# Placa_5_Sensores.net
KiCad netlist of a schematic drawn in Altium Designer
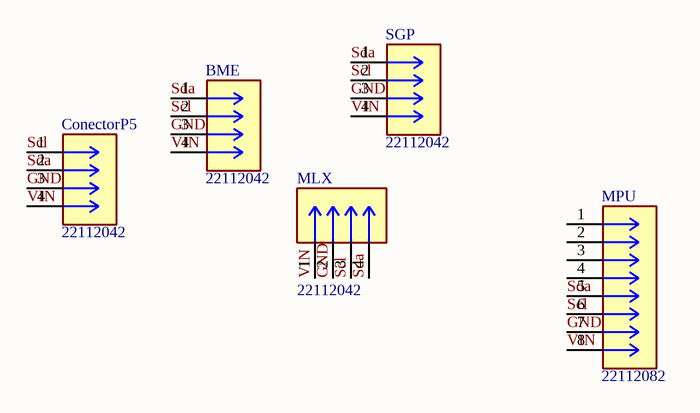
[diagram p0: Placa 5 (Sensores).SchDoc]

(export (version "E")
  (design (tool "Eeschema 10.0.6"))
  (components
    (comp (ref "BME")
      (value "22112042")
      (footprint "CONN_A-6373-04A_MOL")
      (libsource (lib "22112042") (part "22112042"))
    )
    (comp (ref "ConectorP5")
      (value "22112042")
      (footprint "CONN_A-6373-04A_MOL")
      (libsource (lib "22112042") (part "22112042"))
    )
    (comp (ref "MLX")
      (value "22112042")
      (footprint "CONN_A-6373-04A_MOL")
      (libsource (lib "") (part "22112042_1"))
    )
    (comp (ref "MPU")
      (value "22112082")
      (footprint "CONN_A-6373-08A_MOL")
      (description "KKÂ® 254 Solid Header, Vertical, with Friction Lock, 8 Circuits, Gold (Au) Plating")
      (fields (field (name "MF") "Molex") (field (name "MP") "22-11-2082"))
      (libsource (lib "22112082") (part "22112082"))
    )
    (comp (ref "SGP")
      (value "22112042")
      (footprint "CONN_A-6373-04A_MOL")
      (libsource (lib "22112042") (part "22112042"))
    )
  )
  (nets
    (net (code "1") (name "/GND") (class "Default")
      (node (ref "BME") (pin "3") (pinfunction "3_3") (pintype "passive"))
      (node (ref "ConectorP5") (pin "3") (pinfunction "3_3") (pintype "passive"))
      (node (ref "MLX") (pin "2") (pinfunction "2_2") (pintype "passive"))
      (node (ref "MPU") (pin "7") (pinfunction "7_7") (pintype "passive"))
      (node (ref "SGP") (pin "3") (pinfunction "3_3") (pintype "passive"))
    )
    (net (code "2") (name "/Scl") (class "Default")
      (node (ref "BME") (pin "2") (pinfunction "2_2") (pintype "passive"))
      (node (ref "ConectorP5") (pin "1") (pinfunction "1_1") (pintype "passive"))
      (node (ref "MLX") (pin "3") (pinfunction "3_3") (pintype "passive"))
      (node (ref "MPU") (pin "6") (pinfunction "6_6") (pintype "passive"))
      (node (ref "SGP") (pin "2") (pinfunction "2_2") (pintype "passive"))
    )
    (net (code "3") (name "/Sda") (class "Default")
      (node (ref "BME") (pin "1") (pinfunction "1_1") (pintype "passive"))
      (node (ref "ConectorP5") (pin "2") (pinfunction "2_2") (pintype "passive"))
      (node (ref "MLX") (pin "4") (pinfunction "4_4") (pintype "passive"))
      (node (ref "MPU") (pin "5") (pinfunction "5_5") (pintype "passive"))
      (node (ref "SGP") (pin "1") (pinfunction "1_1") (pintype "passive"))
    )
    (net (code "4") (name "/VIN") (class "Default")
      (node (ref "BME") (pin "4") (pinfunction "4_4") (pintype "passive"))
      (node (ref "ConectorP5") (pin "4") (pinfunction "4_4") (pintype "passive"))
      (node (ref "MLX") (pin "1") (pinfunction "1_1") (pintype "passive"))
      (node (ref "MPU") (pin "8") (pinfunction "8_8") (pintype "passive"))
      (node (ref "SGP") (pin "4") (pinfunction "4_4") (pintype "passive"))
    )
    (net (code "5") (name "unconnected-(MPU-Pad1)") (class "Default")
      (node (ref "MPU") (pin "1") (pinfunction "1_1") (pintype "passive"))
    )
    (net (code "6") (name "unconnected-(MPU-Pad2)") (class "Default")
      (node (ref "MPU") (pin "2") (pinfunction "2_2") (pintype "passive"))
    )
    (net (code "7") (name "unconnected-(MPU-Pad3)") (class "Default")
      (node (ref "MPU") (pin "3") (pinfunction "3_3") (pintype "passive"))
    )
    (net (code "8") (name "unconnected-(MPU-Pad4)") (class "Default")
      (node (ref "MPU") (pin "4") (pinfunction "4_4") (pintype "passive"))
    )
  )
)
